# main.net
KiCad netlist of a schematic drawn in EAGLE
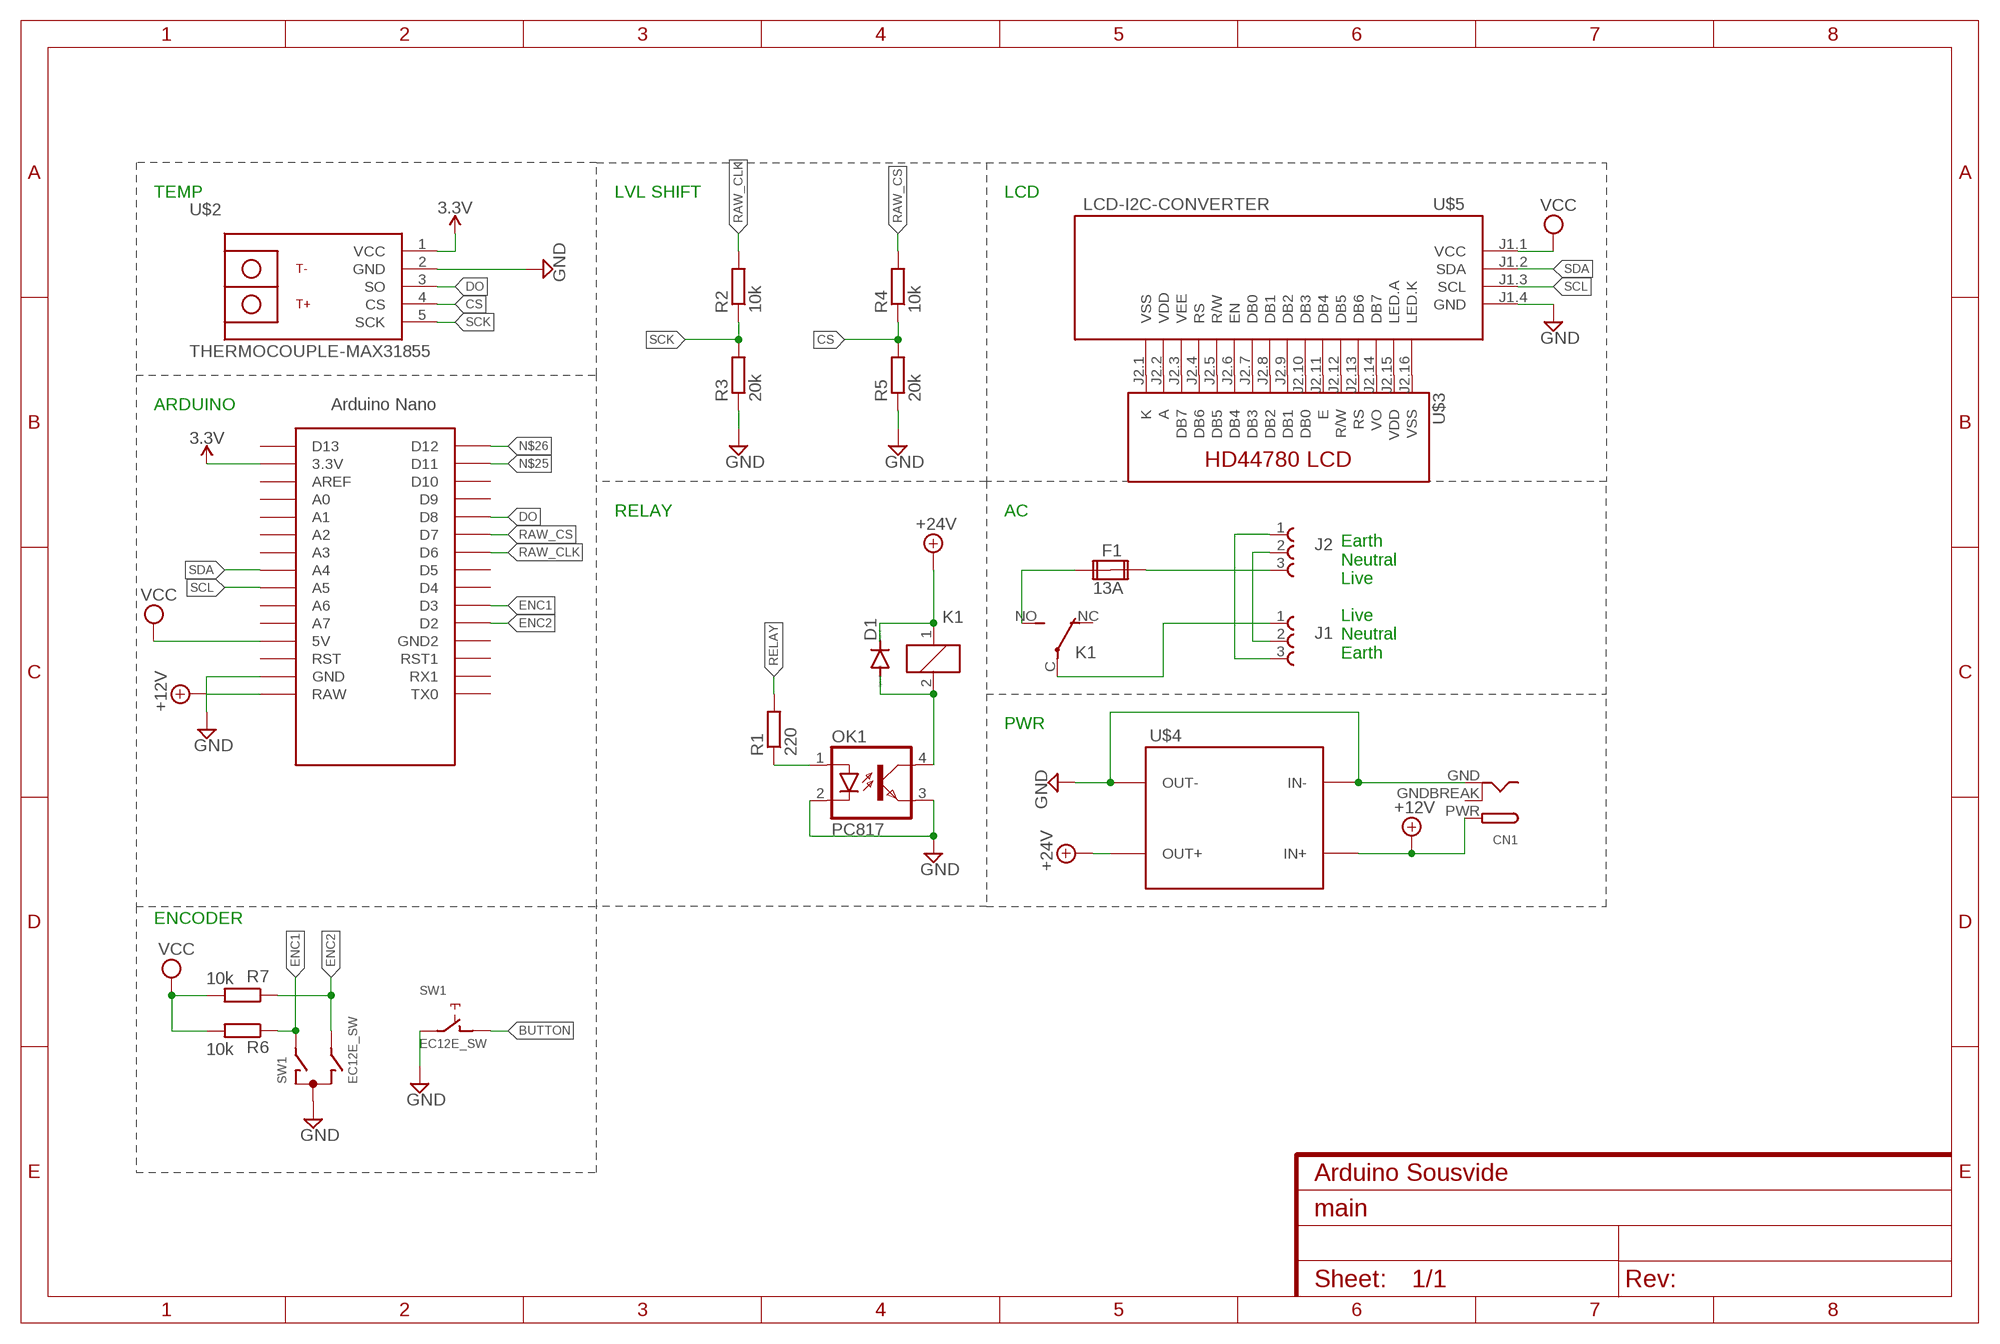
[diagram p0: schematic, sheet 1]

(export (version "E")
  (design (tool "Eeschema 10.0.6"))
  (components
    (comp (ref "CN1")
      (value "DCBARRELPTH")
      (footprint "eagle-import:DCJACK_2MM_PTH")
      (libsource (lib "eagle-import") (part "DCBARRELPTH"))
    )
    (comp (ref "D1")
      (value "1N4004")
      (footprint "eagle-import:DO41-10")
      (libsource (lib "eagle-import") (part "1N4004"))
    )
    (comp (ref "F1")
      (value "13A")
      (footprint "eagle-import:FUSE1")
      (libsource (lib "eagle-import") (part "FUSE2P"))
    )
    (comp (ref "J1")
      (value "691241710003")
      (footprint "eagle-import:691241710003")
      (libsource (lib "eagle-import") (part "691241710003"))
    )
    (comp (ref "J2")
      (value "691241710003")
      (footprint "eagle-import:691241710003")
      (libsource (lib "eagle-import") (part "691241710003"))
    )
    (comp (ref "K1")
      (value "CQ1-12V")
      (footprint "eagle-import:CQ1")
      (libsource (lib "eagle-import") (part "CQ1-12V"))
    )
    (comp (ref "OK1")
      (value "PC817")
      (footprint "eagle-import:DIL04")
      (fields (field (name "MPN") "PC817X4J000F"))
      (libsource (lib "eagle-import") (part "PC817"))
    )
    (comp (ref "R1")
      (value "220")
      (footprint "eagle-import:0207_7")
      (libsource (lib "eagle-import") (part "R-EU_0207/7"))
    )
    (comp (ref "R2")
      (value "10k")
      (footprint "eagle-import:0207_7")
      (libsource (lib "eagle-import") (part "R-EU_0207/7"))
    )
    (comp (ref "R3")
      (value "20k")
      (footprint "eagle-import:0207_7")
      (libsource (lib "eagle-import") (part "R-EU_0207/7"))
    )
    (comp (ref "R4")
      (value "10k")
      (footprint "eagle-import:0207_7")
      (libsource (lib "eagle-import") (part "R-EU_0207/7"))
    )
    (comp (ref "R5")
      (value "20k")
      (footprint "eagle-import:0207_7")
      (libsource (lib "eagle-import") (part "R-EU_0207/7"))
    )
    (comp (ref "R6")
      (value "10k")
      (footprint "eagle-import:0207_7")
      (libsource (lib "eagle-import") (part "R-EU_0207/7"))
    )
    (comp (ref "R7")
      (value "10k")
      (footprint "eagle-import:0207_7")
      (libsource (lib "eagle-import") (part "R-EU_0207/7"))
    )
    (comp (ref "SW1")
      (value "EC12E_SW")
      (footprint "eagle-import:ALPS_EC12E_SW")
      (fields (field (name "MPN") "EC12E2424407"))
      (libsource (lib "eagle-import") (part "EC12E_SW"))
    )
    (comp (ref "U$1")
      (value "NANO")
      (footprint "eagle-import:NANO")
      (libsource (lib "eagle-import") (part "NANO"))
    )
    (comp (ref "U$2")
      (value "THERMOCOUPLE-MAX31855")
      (footprint "eagle-import:THERMOCOUPLE-MAX31855")
      (libsource (lib "eagle-import") (part "THERMOCOUPLE-MAX31855"))
    )
    (comp (ref "U$3")
      (value "LCD-HD4478016X2-4-HOLES-BL16X2-4-HOLES-BL")
      (footprint "eagle-import:LCD-16X2-4HOLES-BL")
      (libsource (lib "eagle-import") (part "LCD-HD4478016X2-4-HOLES-BL16X2-4-HOLES-BL"))
    )
    (comp (ref "U$4")
      (value "DC-DC-STEP-DOWN-LM2596")
      (footprint "eagle-import:DC-DC-STEP-DOWN-LM2596")
      (libsource (lib "eagle-import") (part "DC-DC-STEP-DOWN-LM2596"))
    )
    (comp (ref "U$5")
      (value "LCD-I2C-CONVERTER")
      (footprint "eagle-import:LCD-I2C-CONVERTER")
      (libsource (lib "eagle-import") (part "LCD-I2C-CONVERTER"))
    )
  )
  (nets
    (net (code "1") (name "+12V") (class "Default")
      (node (ref "CN1") (pin "PWR") (pinfunction "PWR_PWR") (pintype "power_in"))
      (node (ref "U$1") (pin "RAW") (pinfunction "RAW_RAW") (pintype "bidirectional"))
      (node (ref "U$4") (pin "IN+") (pinfunction "IN+_IN+") (pintype "bidirectional"))
    )
    (net (code "2") (name "+24V") (class "Default")
      (node (ref "D1") (pin "C") (pinfunction "C_C") (pintype "passive"))
      (node (ref "K1") (pin "1") (pinfunction "1_1") (pintype "passive"))
      (node (ref "U$4") (pin "OUT+") (pinfunction "OUT+_OUT+") (pintype "bidirectional"))
    )
    (net (code "3") (name "/GNDBREAK") (class "Default")
      (node (ref "CN1") (pin "GNDBREAK") (pinfunction "GNDBREAK_GNDBREAK") (pintype "power_in"))
    )
    (net (code "4") (name "3.3V") (class "Default")
      (node (ref "U$1") (pin "3.3V") (pinfunction "3.3V_3.3V") (pintype "bidirectional"))
      (node (ref "U$2") (pin "1") (pinfunction "VCC_1") (pintype "power_in"))
    )
    (net (code "5") (name "BUTTON") (class "Default")
      (node (ref "SW1") (pin "D") (pinfunction "1_D") (pintype "passive"))
    )
    (net (code "6") (name "CS") (class "Default")
      (node (ref "R4") (pin "1") (pinfunction "1_1") (pintype "passive"))
      (node (ref "R5") (pin "2") (pinfunction "2_2") (pintype "passive"))
      (node (ref "U$2") (pin "4") (pinfunction "CS_4") (pintype "bidirectional"))
    )
    (net (code "7") (name "DO") (class "Default")
      (node (ref "U$1") (pin "D8") (pinfunction "D8_D8") (pintype "bidirectional"))
      (node (ref "U$2") (pin "3") (pinfunction "SO_3") (pintype "bidirectional"))
    )
    (net (code "8") (name "ENC1") (class "Default")
      (node (ref "R6") (pin "1") (pinfunction "1_1") (pintype "passive"))
      (node (ref "SW1") (pin "A") (pinfunction "A_A") (pintype "passive"))
      (node (ref "U$1") (pin "D3") (pinfunction "D3_D3") (pintype "bidirectional"))
    )
    (net (code "9") (name "ENC2") (class "Default")
      (node (ref "R7") (pin "1") (pinfunction "1_1") (pintype "passive"))
      (node (ref "SW1") (pin "B") (pinfunction "B_B") (pintype "passive"))
      (node (ref "U$1") (pin "D2") (pinfunction "D2_D2") (pintype "bidirectional"))
    )
    (net (code "10") (name "GND") (class "Default")
      (node (ref "CN1") (pin "GND") (pinfunction "GND_GND") (pintype "power_in"))
      (node (ref "OK1") (pin "2") (pinfunction "C_2") (pintype "passive"))
      (node (ref "OK1") (pin "3") (pinfunction "EMIT_3") (pintype "passive"))
      (node (ref "R3") (pin "1") (pinfunction "1_1") (pintype "passive"))
      (node (ref "R5") (pin "1") (pinfunction "1_1") (pintype "passive"))
      (node (ref "SW1") (pin "C") (pinfunction "C_C") (pintype "passive"))
      (node (ref "SW1") (pin "E") (pinfunction "2_E") (pintype "passive"))
      (node (ref "U$1") (pin "GND") (pinfunction "GND_GND") (pintype "bidirectional"))
      (node (ref "U$2") (pin "2") (pinfunction "GND_2") (pintype "output"))
      (node (ref "U$4") (pin "IN-") (pinfunction "IN-_IN-") (pintype "bidirectional"))
      (node (ref "U$4") (pin "OUT-") (pinfunction "OUT-_OUT-") (pintype "bidirectional"))
      (node (ref "U$5") (pin "J1.4") (pinfunction "GND_J1.4") (pintype "power_in"))
    )
    (net (code "11") (name "N$25") (class "Default")
      (node (ref "U$1") (pin "D11") (pinfunction "D11_D11") (pintype "bidirectional"))
    )
    (net (code "12") (name "N$26") (class "Default")
      (node (ref "U$1") (pin "D12") (pinfunction "D12_D12") (pintype "bidirectional"))
    )
    (net (code "13") (name "Net-(F1-Pad2A)") (class "Default")
      (node (ref "F1") (pin "2A") (pinfunction "2A_2A") (pintype "passive"))
      (node (ref "J2") (pin "3") (pinfunction "3_3") (pintype "passive"))
    )
    (net (code "14") (name "Net-(J1-Pad2)") (class "Default")
      (node (ref "J1") (pin "2") (pinfunction "2_2") (pintype "passive"))
      (node (ref "J2") (pin "2") (pinfunction "2_2") (pintype "passive"))
    )
    (net (code "15") (name "Net-(J1-Pad3)") (class "Default")
      (node (ref "J1") (pin "3") (pinfunction "3_3") (pintype "passive"))
      (node (ref "J2") (pin "1") (pinfunction "1_1") (pintype "passive"))
    )
    (net (code "16") (name "Net-(K1B-P)") (class "Default")
      (node (ref "J1") (pin "1") (pinfunction "1_1") (pintype "passive"))
      (node (ref "K1") (pin "C") (pinfunction "P_C") (pintype "passive"))
    )
    (net (code "17") (name "Net-(K1B-S)") (class "Default")
      (node (ref "F1") (pin "1A") (pinfunction "1A_1A") (pintype "passive"))
      (node (ref "K1") (pin "NO") (pinfunction "S_NO") (pintype "passive"))
    )
    (net (code "18") (name "Net-(OK1-A)") (class "Default")
      (node (ref "OK1") (pin "1") (pinfunction "A_1") (pintype "passive"))
      (node (ref "R1") (pin "1") (pinfunction "1_1") (pintype "passive"))
    )
    (net (code "19") (name "Net-(OK1-COL)") (class "Default")
      (node (ref "D1") (pin "A") (pinfunction "A_A") (pintype "passive"))
      (node (ref "K1") (pin "2") (pinfunction "2_2") (pintype "passive"))
      (node (ref "OK1") (pin "4") (pinfunction "COL_4") (pintype "passive"))
    )
    (net (code "20") (name "Net-(U$3-A)") (class "Default")
      (node (ref "U$3") (pin "15") (pinfunction "A_15") (pintype "power_in"))
      (node (ref "U$5") (pin "J2.2") (pinfunction "VDD_J2.2") (pintype "bidirectional"))
    )
    (net (code "21") (name "Net-(U$3-DB0)") (class "Default")
      (node (ref "U$3") (pin "7") (pinfunction "DB0_7") (pintype "bidirectional"))
      (node (ref "U$5") (pin "J2.10") (pinfunction "DB3_J2.10") (pintype "bidirectional"))
    )
    (net (code "22") (name "Net-(U$3-DB1)") (class "Default")
      (node (ref "U$3") (pin "8") (pinfunction "DB1_8") (pintype "bidirectional"))
      (node (ref "U$5") (pin "J2.9") (pinfunction "DB2_J2.9") (pintype "bidirectional"))
    )
    (net (code "23") (name "Net-(U$3-DB2)") (class "Default")
      (node (ref "U$3") (pin "9") (pinfunction "DB2_9") (pintype "bidirectional"))
      (node (ref "U$5") (pin "J2.8") (pinfunction "DB1_J2.8") (pintype "bidirectional"))
    )
    (net (code "24") (name "Net-(U$3-DB3)") (class "Default")
      (node (ref "U$3") (pin "10") (pinfunction "DB3_10") (pintype "bidirectional"))
      (node (ref "U$5") (pin "J2.7") (pinfunction "DB0_J2.7") (pintype "bidirectional"))
    )
    (net (code "25") (name "Net-(U$3-DB4)") (class "Default")
      (node (ref "U$3") (pin "11") (pinfunction "DB4_11") (pintype "bidirectional"))
      (node (ref "U$5") (pin "J2.6") (pinfunction "EN_J2.6") (pintype "bidirectional"))
    )
    (net (code "26") (name "Net-(U$3-DB5)") (class "Default")
      (node (ref "U$3") (pin "12") (pinfunction "DB5_12") (pintype "bidirectional"))
      (node (ref "U$5") (pin "J2.5") (pinfunction "R/W_J2.5") (pintype "bidirectional"))
    )
    (net (code "27") (name "Net-(U$3-DB6)") (class "Default")
      (node (ref "U$3") (pin "13") (pinfunction "DB6_13") (pintype "bidirectional"))
      (node (ref "U$5") (pin "J2.4") (pinfunction "RS_J2.4") (pintype "bidirectional"))
    )
    (net (code "28") (name "Net-(U$3-DB7)") (class "Default")
      (node (ref "U$3") (pin "14") (pinfunction "DB7_14") (pintype "bidirectional"))
      (node (ref "U$5") (pin "J2.3") (pinfunction "VEE_J2.3") (pintype "bidirectional"))
    )
    (net (code "29") (name "Net-(U$3-E)") (class "Default")
      (node (ref "U$3") (pin "6") (pinfunction "E_6") (pintype "input"))
      (node (ref "U$5") (pin "J2.11") (pinfunction "DB4_J2.11") (pintype "bidirectional"))
    )
    (net (code "30") (name "Net-(U$3-K)") (class "Default")
      (node (ref "U$3") (pin "16") (pinfunction "K_16") (pintype "power_in"))
      (node (ref "U$5") (pin "J2.1") (pinfunction "VSS_J2.1") (pintype "bidirectional"))
    )
    (net (code "31") (name "Net-(U$3-RS)") (class "Default")
      (node (ref "U$3") (pin "4") (pinfunction "RS_4") (pintype "input"))
      (node (ref "U$5") (pin "J2.13") (pinfunction "DB6_J2.13") (pintype "bidirectional"))
    )
    (net (code "32") (name "Net-(U$3-R{slash}W)") (class "Default")
      (node (ref "U$3") (pin "5") (pinfunction "R/W_5") (pintype "input"))
      (node (ref "U$5") (pin "J2.12") (pinfunction "DB5_J2.12") (pintype "bidirectional"))
    )
    (net (code "33") (name "Net-(U$3-VDD)") (class "Default")
      (node (ref "U$3") (pin "2") (pinfunction "VDD_2") (pintype "power_in"))
      (node (ref "U$5") (pin "J2.15") (pinfunction "LED.A_J2.15") (pintype "bidirectional"))
    )
    (net (code "34") (name "Net-(U$3-VO)") (class "Default")
      (node (ref "U$3") (pin "3") (pinfunction "VO_3") (pintype "bidirectional"))
      (node (ref "U$5") (pin "J2.14") (pinfunction "DB7_J2.14") (pintype "bidirectional"))
    )
    (net (code "35") (name "Net-(U$3-VSS)") (class "Default")
      (node (ref "U$3") (pin "1") (pinfunction "VSS_1") (pintype "power_in"))
      (node (ref "U$5") (pin "J2.16") (pinfunction "LED.K_J2.16") (pintype "bidirectional"))
    )
    (net (code "36") (name "RAW_CLK") (class "Default")
      (node (ref "R2") (pin "2") (pinfunction "2_2") (pintype "passive"))
      (node (ref "U$1") (pin "D6") (pinfunction "D6_D6") (pintype "bidirectional"))
    )
    (net (code "37") (name "RAW_CS") (class "Default")
      (node (ref "R4") (pin "2") (pinfunction "2_2") (pintype "passive"))
      (node (ref "U$1") (pin "D7") (pinfunction "D7_D7") (pintype "bidirectional"))
    )
    (net (code "38") (name "RELAY") (class "Default")
      (node (ref "R1") (pin "2") (pinfunction "2_2") (pintype "passive"))
    )
    (net (code "39") (name "SCK") (class "Default")
      (node (ref "R2") (pin "1") (pinfunction "1_1") (pintype "passive"))
      (node (ref "R3") (pin "2") (pinfunction "2_2") (pintype "passive"))
      (node (ref "U$2") (pin "5") (pinfunction "SCK_5") (pintype "bidirectional"))
    )
    (net (code "40") (name "SCL") (class "Default")
      (node (ref "U$1") (pin "A5") (pinfunction "A5_A5") (pintype "bidirectional"))
      (node (ref "U$5") (pin "J1.3") (pinfunction "SCL_J1.3") (pintype "bidirectional"))
    )
    (net (code "41") (name "SDA") (class "Default")
      (node (ref "U$1") (pin "A4") (pinfunction "A4_A4") (pintype "bidirectional"))
      (node (ref "U$5") (pin "J1.2") (pinfunction "SDA_J1.2") (pintype "bidirectional"))
    )
    (net (code "42") (name "VCC") (class "Default")
      (node (ref "R6") (pin "2") (pinfunction "2_2") (pintype "passive"))
      (node (ref "R7") (pin "2") (pinfunction "2_2") (pintype "passive"))
      (node (ref "U$1") (pin "5V") (pinfunction "5V_5V") (pintype "bidirectional"))
      (node (ref "U$5") (pin "J1.1") (pinfunction "VCC_J1.1") (pintype "power_in"))
    )
    (net (code "43") (name "unconnected-(F1-Pad1B)") (class "Default")
      (node (ref "F1") (pin "1B") (pinfunction "1B_1B") (pintype "passive"))
    )
    (net (code "44") (name "unconnected-(F1-Pad2B)") (class "Default")
      (node (ref "F1") (pin "2B") (pinfunction "2B_2B") (pintype "passive"))
    )
    (net (code "45") (name "unconnected-(K1B-O-PadNC)") (class "Default")
      (node (ref "K1") (pin "NC") (pinfunction "O_NC") (pintype "passive"))
    )
    (net (code "46") (name "unconnected-(U$1-GND2-PadGND1)") (class "Default")
      (node (ref "U$1") (pin "GND1") (pinfunction "GND2_GND1") (pintype "bidirectional"))
    )
    (net (code "47") (name "unconnected-(U$1-PadA0)") (class "Default")
      (node (ref "U$1") (pin "A0") (pinfunction "A0_A0") (pintype "bidirectional"))
    )
    (net (code "48") (name "unconnected-(U$1-PadA1)") (class "Default")
      (node (ref "U$1") (pin "A1") (pinfunction "A1_A1") (pintype "bidirectional"))
    )
    (net (code "49") (name "unconnected-(U$1-PadA2)") (class "Default")
      (node (ref "U$1") (pin "A2") (pinfunction "A2_A2") (pintype "bidirectional"))
    )
    (net (code "50") (name "unconnected-(U$1-PadA3)") (class "Default")
      (node (ref "U$1") (pin "A3") (pinfunction "A3_A3") (pintype "bidirectional"))
    )
    (net (code "51") (name "unconnected-(U$1-PadA6)") (class "Default")
      (node (ref "U$1") (pin "A6") (pinfunction "A6_A6") (pintype "bidirectional"))
    )
    (net (code "52") (name "unconnected-(U$1-PadA7)") (class "Default")
      (node (ref "U$1") (pin "A7") (pinfunction "A7_A7") (pintype "bidirectional"))
    )
    (net (code "53") (name "unconnected-(U$1-PadAREF)") (class "Default")
      (node (ref "U$1") (pin "AREF") (pinfunction "AREF_AREF") (pintype "bidirectional"))
    )
    (net (code "54") (name "unconnected-(U$1-PadD4)") (class "Default")
      (node (ref "U$1") (pin "D4") (pinfunction "D4_D4") (pintype "bidirectional"))
    )
    (net (code "55") (name "unconnected-(U$1-PadD5)") (class "Default")
      (node (ref "U$1") (pin "D5") (pinfunction "D5_D5") (pintype "bidirectional"))
    )
    (net (code "56") (name "unconnected-(U$1-PadD9)") (class "Default")
      (node (ref "U$1") (pin "D9") (pinfunction "D9_D9") (pintype "bidirectional"))
    )
    (net (code "57") (name "unconnected-(U$1-PadD10)") (class "Default")
      (node (ref "U$1") (pin "D10") (pinfunction "D10_D10") (pintype "bidirectional"))
    )
    (net (code "58") (name "unconnected-(U$1-PadD13)") (class "Default")
      (node (ref "U$1") (pin "D13") (pinfunction "D13_D13") (pintype "bidirectional"))
    )
    (net (code "59") (name "unconnected-(U$1-PadICSP1)") (class "Default")
      (node (ref "U$1") (pin "ICSP1") (pinfunction "ICSP1_ICSP1") (pintype "bidirectional"))
    )
    (net (code "60") (name "unconnected-(U$1-PadICSP2)") (class "Default")
      (node (ref "U$1") (pin "ICSP2") (pinfunction "ICSP2_ICSP2") (pintype "bidirectional"))
    )
    (net (code "61") (name "unconnected-(U$1-PadICSP3)") (class "Default")
      (node (ref "U$1") (pin "ICSP3") (pinfunction "ICSP3_ICSP3") (pintype "bidirectional"))
    )
    (net (code "62") (name "unconnected-(U$1-PadICSP4)") (class "Default")
      (node (ref "U$1") (pin "ICSP4") (pinfunction "ICSP4_ICSP4") (pintype "bidirectional"))
    )
    (net (code "63") (name "unconnected-(U$1-PadICSP5)") (class "Default")
      (node (ref "U$1") (pin "ICSP5") (pinfunction "ICSP5_ICSP5") (pintype "bidirectional"))
    )
    (net (code "64") (name "unconnected-(U$1-PadICSP6)") (class "Default")
      (node (ref "U$1") (pin "ICSP6") (pinfunction "ICSP6_ICSP6") (pintype "bidirectional"))
    )
    (net (code "65") (name "unconnected-(U$1-PadRST)") (class "Default")
      (node (ref "U$1") (pin "RST") (pinfunction "RST_RST") (pintype "bidirectional"))
    )
    (net (code "66") (name "unconnected-(U$1-PadRST1)") (class "Default")
      (node (ref "U$1") (pin "RST1") (pinfunction "RST1_RST1") (pintype "bidirectional"))
    )
    (net (code "67") (name "unconnected-(U$1-PadRX1)") (class "Default")
      (node (ref "U$1") (pin "RX1") (pinfunction "RX1_RX1") (pintype "bidirectional"))
    )
    (net (code "68") (name "unconnected-(U$1-PadTX0)") (class "Default")
      (node (ref "U$1") (pin "TX0") (pinfunction "TX0_TX0") (pintype "bidirectional"))
    )
  )
)
